# DC_BOOST_PART.net
KiCad netlist of a schematic drawn in Altium Designer
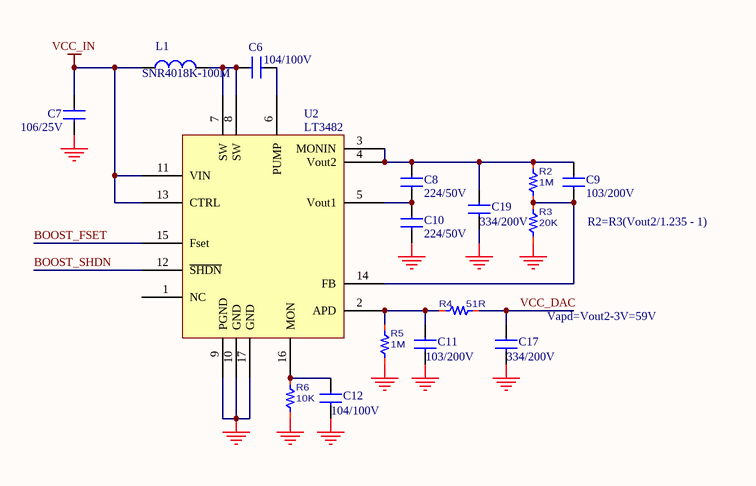
[diagram p0: DC_BOOST_PART.SchDoc]

(export (version "E")
  (design (tool "Eeschema 10.0.6"))
  (components
    (comp (ref "C6")
      (value "104/100V")
      (footprint "0603C/1")
      (description "Capacitor")
      (libsource (lib "其他常用器件") (part "电容"))
    )
    (comp (ref "C7")
      (value "106/25V")
      (footprint "0603C/1")
      (description "Capacitor")
      (libsource (lib "其他常用器件") (part "电容"))
    )
    (comp (ref "C8")
      (value "224/50V")
      (footprint "0603C/1")
      (description "Capacitor")
      (libsource (lib "其他常用器件") (part "电容"))
    )
    (comp (ref "C9")
      (value "103/200V")
      (footprint "0603C/1")
      (description "Capacitor")
      (libsource (lib "其他常用器件") (part "电容"))
    )
    (comp (ref "C10")
      (value "224/50V")
      (footprint "0603C/1")
      (description "Capacitor")
      (libsource (lib "其他常用器件") (part "电容"))
    )
    (comp (ref "C11")
      (value "103/200V")
      (footprint "0603c/1")
      (description "Capacitor")
      (libsource (lib "其他常用器件") (part "电容"))
    )
    (comp (ref "C12")
      (value "104/100V")
      (footprint "0603c/1")
      (description "Capacitor")
      (libsource (lib "其他常用器件") (part "电容"))
    )
    (comp (ref "C17")
      (value "334/200V")
      (footprint "1210c")
      (description "Capacitor")
      (libsource (lib "其他常用器件") (part "电容"))
    )
    (comp (ref "C19")
      (value "334/200V")
      (footprint "1210c")
      (description "Capacitor")
      (libsource (lib "其他常用器件") (part "电容"))
    )
    (comp (ref "L1")
      (value "SNR4018K-100M")
      (footprint "L3.0-W3.0")
      (description "Inductor")
      (libsource (lib "其他常用器件") (part "电感"))
    )
    (comp (ref "R2")
      (value "1M")
      (footprint "0603R/1")
      (description "Resistor")
      (libsource (lib "其他常用器件") (part "RESS1"))
    )
    (comp (ref "R3")
      (value "20K")
      (footprint "0603R/1")
      (description "Resistor")
      (libsource (lib "其他常用器件") (part "RESS1"))
    )
    (comp (ref "R4")
      (value "51R")
      (footprint "0603R/1")
      (description "Resistor")
      (libsource (lib "其他常用器件") (part "RESS1"))
    )
    (comp (ref "R5")
      (value "1M")
      (footprint "0603R/1")
      (description "Resistor")
      (libsource (lib "其他常用器件") (part "RESS1"))
    )
    (comp (ref "R6")
      (value "10K")
      (footprint "0603R/1")
      (description "Resistor")
      (libsource (lib "其他常用器件") (part "RESS1"))
    )
    (comp (ref "U2")
      (value "LT3482")
      (footprint "QFN-16_L3.0-W3.0-P0.50-BL-EP1.7")
      (libsource (lib "其他常用器件") (part "LT3482"))
    )
  )
  (nets
    (net (code "1") (name "/BOOST_FSET") (class "Default")
      (node (ref "U2") (pin "15") (pinfunction "Fset_15") (pintype "passive"))
    )
    (net (code "2") (name "/BOOST_SHDN") (class "Default")
      (node (ref "U2") (pin "12") (pinfunction "~{SHDN}_12") (pintype "passive"))
    )
    (net (code "3") (name "/VCC_DAC") (class "Default")
      (node (ref "C17") (pin "1") (pinfunction "1_1") (pintype "passive"))
      (node (ref "R4") (pin "1") (pinfunction "1_1") (pintype "passive"))
    )
    (net (code "4") (name "GND") (class "Default")
      (node (ref "C10") (pin "2") (pinfunction "2_2") (pintype "passive"))
      (node (ref "C11") (pin "2") (pinfunction "2_2") (pintype "passive"))
      (node (ref "C12") (pin "2") (pinfunction "2_2") (pintype "passive"))
      (node (ref "C17") (pin "2") (pinfunction "2_2") (pintype "passive"))
      (node (ref "C19") (pin "2") (pinfunction "2_2") (pintype "passive"))
      (node (ref "C7") (pin "2") (pinfunction "2_2") (pintype "passive"))
      (node (ref "R3") (pin "1") (pinfunction "1_1") (pintype "passive"))
      (node (ref "R5") (pin "2") (pinfunction "2_2") (pintype "passive"))
      (node (ref "R6") (pin "1") (pinfunction "1_1") (pintype "passive"))
      (node (ref "U2") (pin "10") (pinfunction "GND_10") (pintype "passive"))
      (node (ref "U2") (pin "17") (pinfunction "GND_17") (pintype "passive"))
      (node (ref "U2") (pin "9") (pinfunction "PGND_9") (pintype "passive"))
    )
    (net (code "5") (name "Net-(C6-Pad2)") (class "Default")
      (node (ref "C6") (pin "2") (pinfunction "2_2") (pintype "passive"))
      (node (ref "L1") (pin "2") (pinfunction "2_2") (pintype "passive"))
      (node (ref "U2") (pin "7") (pinfunction "SW_7") (pintype "passive"))
      (node (ref "U2") (pin "8") (pinfunction "SW_8") (pintype "passive"))
    )
    (net (code "6") (name "Net-(U2-APD)") (class "Default")
      (node (ref "C11") (pin "1") (pinfunction "1_1") (pintype "passive"))
      (node (ref "R4") (pin "2") (pinfunction "2_2") (pintype "passive"))
      (node (ref "R5") (pin "1") (pinfunction "1_1") (pintype "passive"))
      (node (ref "U2") (pin "2") (pinfunction "APD_2") (pintype "passive"))
    )
    (net (code "7") (name "Net-(U2-FB)") (class "Default")
      (node (ref "C9") (pin "2") (pinfunction "2_2") (pintype "passive"))
      (node (ref "R2") (pin "1") (pinfunction "1_1") (pintype "passive"))
      (node (ref "R3") (pin "2") (pinfunction "2_2") (pintype "passive"))
      (node (ref "U2") (pin "14") (pinfunction "FB_14") (pintype "passive"))
    )
    (net (code "8") (name "Net-(U2-MON)") (class "Default")
      (node (ref "C12") (pin "1") (pinfunction "1_1") (pintype "passive"))
      (node (ref "R6") (pin "2") (pinfunction "2_2") (pintype "passive"))
      (node (ref "U2") (pin "16") (pinfunction "MON_16") (pintype "passive"))
    )
    (net (code "9") (name "Net-(U2-MONIN)") (class "Default")
      (node (ref "C19") (pin "1") (pinfunction "1_1") (pintype "passive"))
      (node (ref "C8") (pin "1") (pinfunction "1_1") (pintype "passive"))
      (node (ref "C9") (pin "1") (pinfunction "1_1") (pintype "passive"))
      (node (ref "R2") (pin "2") (pinfunction "2_2") (pintype "passive"))
      (node (ref "U2") (pin "3") (pinfunction "MONIN_3") (pintype "passive"))
      (node (ref "U2") (pin "4") (pinfunction "Vout2_4") (pintype "passive"))
    )
    (net (code "10") (name "Net-(U2-PUMP)") (class "Default")
      (node (ref "C6") (pin "1") (pinfunction "1_1") (pintype "passive"))
      (node (ref "U2") (pin "6") (pinfunction "PUMP_6") (pintype "passive"))
    )
    (net (code "11") (name "Net-(U2-Vout1)") (class "Default")
      (node (ref "C10") (pin "1") (pinfunction "1_1") (pintype "passive"))
      (node (ref "C8") (pin "2") (pinfunction "2_2") (pintype "passive"))
      (node (ref "U2") (pin "5") (pinfunction "Vout1_5") (pintype "passive"))
    )
    (net (code "12") (name "VCC_IN") (class "Default")
      (node (ref "C7") (pin "1") (pinfunction "1_1") (pintype "passive"))
      (node (ref "L1") (pin "1") (pinfunction "1_1") (pintype "passive"))
      (node (ref "U2") (pin "11") (pinfunction "VIN_11") (pintype "passive"))
      (node (ref "U2") (pin "13") (pinfunction "CTRL_13") (pintype "passive"))
    )
    (net (code "13") (name "unconnected-(U2-NC-Pad1)") (class "Default")
      (node (ref "U2") (pin "1") (pinfunction "NC_1") (pintype "passive"))
    )
  )
)
